# 0_STM32.net
KiCad netlist of a schematic drawn in Altium Designer
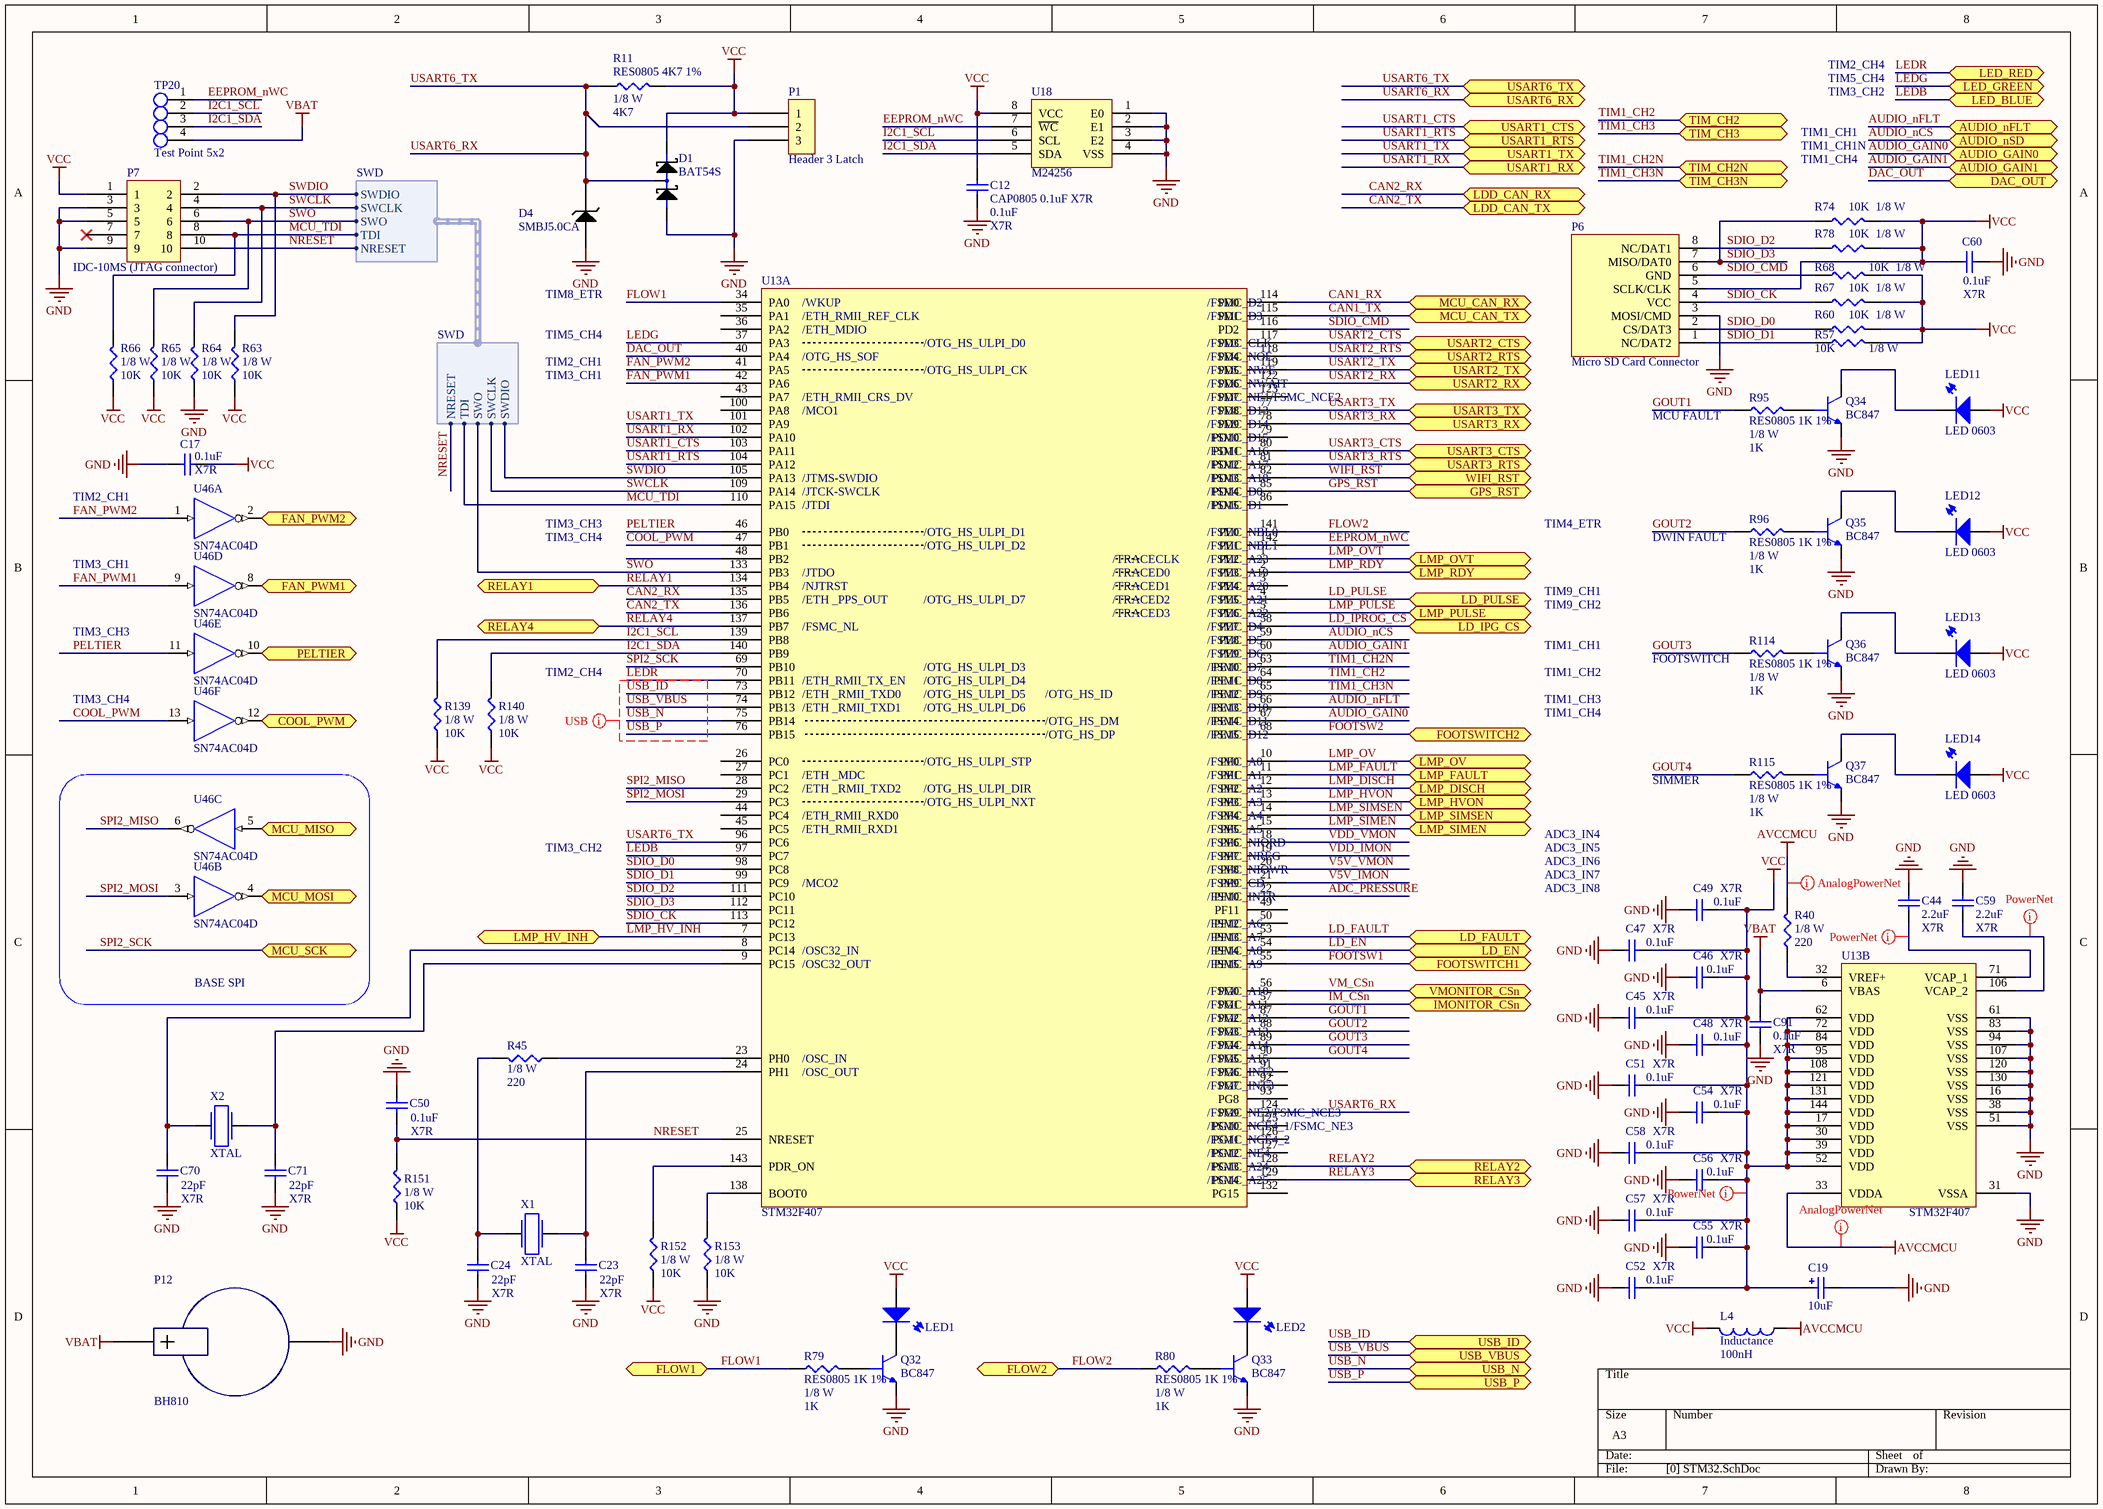
[diagram p0: [0] STM32.SchDoc]

(export (version "E")
  (design (tool "Eeschema 10.0.6"))
  (components
    (comp (ref "C12")
      (value "CAP0805 0.1uF X7R")
      (footprint "CAP0805")
      (description "Surface-mount ceramic multilayer capacitor")
      (fields
        (field (name "VOLTAGE") "50V")
        (field (name "TOLERANCE") "5%")
        (field (name "ALTIUM_VALUE") "0.1uF")
        (field (name "TYPE") "X7R")
      )
      (libsource (lib "Capacitors") (part "CAP0805 0.1uF X7R"))
    )
    (comp (ref "C17")
      (value "0.1uF")
      (footprint "CAP0805")
      (description "Surface-mount ceramic multilayer capacitor")
      (fields (field (name "VOLTAGE") "50V") (field (name "TOLERANCE") "10%") (field (name "TYPE") "X7R"))
      (libsource (lib "Capacitors") (part "CAP0805 0.01uF X7R"))
    )
    (comp (ref "C19")
      (value "10uF")
      (footprint "CAPC7343")
      (description "Polarized Capacitor (Radial)")
      (fields (field (name "Comment") "Cap Pol SMD"))
      (libsource (lib "Common Devices") (part "Cap Pol Chip"))
    )
    (comp (ref "C23")
      (value "22pF")
      (footprint "CAP0805")
      (description "Surface-mount ceramic multilayer capacitor")
      (fields (field (name "VOLTAGE") "50V") (field (name "TOLERANCE") "5%") (field (name "TYPE") "X7R"))
      (libsource (lib "Capacitors") (part "CAP0805 22pF X7R"))
    )
    (comp (ref "C24")
      (value "22pF")
      (footprint "CAP0805")
      (description "Surface-mount ceramic multilayer capacitor")
      (fields (field (name "VOLTAGE") "50V") (field (name "TOLERANCE") "5%") (field (name "TYPE") "X7R"))
      (libsource (lib "Capacitors") (part "CAP0805 22pF X7R"))
    )
    (comp (ref "C44")
      (value "2.2uF")
      (footprint "CAP0805")
      (description "Surface-mount ceramic multilayer capacitor")
      (fields (field (name "VOLTAGE") "50V") (field (name "TOLERANCE") "10%") (field (name "TYPE") "X7R"))
      (libsource (lib "Capacitors") (part "CAP0805 0.01uF X7R"))
    )
    (comp (ref "C45")
      (value "0.1uF")
      (footprint "CAP0805")
      (description "Surface-mount ceramic multilayer capacitor")
      (fields (field (name "VOLTAGE") "50V") (field (name "TOLERANCE") "10%") (field (name "TYPE") "X7R"))
      (libsource (lib "Capacitors") (part "CAP0805 0.01uF X7R"))
    )
    (comp (ref "C46")
      (value "0.1uF")
      (footprint "CAP0805")
      (description "Surface-mount ceramic multilayer capacitor")
      (fields (field (name "VOLTAGE") "50V") (field (name "TOLERANCE") "10%") (field (name "TYPE") "X7R"))
      (libsource (lib "Capacitors") (part "CAP0805 0.01uF X7R"))
    )
    (comp (ref "C47")
      (value "0.1uF")
      (footprint "CAP0805")
      (description "Surface-mount ceramic multilayer capacitor")
      (fields (field (name "VOLTAGE") "50V") (field (name "TOLERANCE") "10%") (field (name "TYPE") "X7R"))
      (libsource (lib "Capacitors") (part "CAP0805 0.01uF X7R"))
    )
    (comp (ref "C48")
      (value "0.1uF")
      (footprint "CAP0805")
      (description "Surface-mount ceramic multilayer capacitor")
      (fields (field (name "VOLTAGE") "50V") (field (name "TOLERANCE") "10%") (field (name "TYPE") "X7R"))
      (libsource (lib "Capacitors") (part "CAP0805 0.01uF X7R"))
    )
    (comp (ref "C49")
      (value "0.1uF")
      (footprint "CAP0805")
      (description "Surface-mount ceramic multilayer capacitor")
      (fields (field (name "VOLTAGE") "50V") (field (name "TOLERANCE") "10%") (field (name "TYPE") "X7R"))
      (libsource (lib "Capacitors") (part "CAP0805 0.01uF X7R"))
    )
    (comp (ref "C50")
      (value "0.1uF")
      (footprint "CAP0805")
      (description "Surface-mount ceramic multilayer capacitor")
      (fields (field (name "VOLTAGE") "50V") (field (name "TOLERANCE") "5%") (field (name "TYPE") "X7R"))
      (libsource (lib "Capacitors") (part "CAP0805 0.1uF X7R"))
    )
    (comp (ref "C51")
      (value "0.1uF")
      (footprint "CAP0805")
      (description "Surface-mount ceramic multilayer capacitor")
      (fields (field (name "VOLTAGE") "50V") (field (name "TOLERANCE") "10%") (field (name "TYPE") "X7R"))
      (libsource (lib "Capacitors") (part "CAP0805 0.01uF X7R"))
    )
    (comp (ref "C52")
      (value "0.1uF")
      (footprint "CAP0805")
      (description "Surface-mount ceramic multilayer capacitor")
      (fields (field (name "VOLTAGE") "50V") (field (name "TOLERANCE") "10%") (field (name "TYPE") "X7R"))
      (libsource (lib "Capacitors") (part "CAP0805 0.01uF X7R"))
    )
    (comp (ref "C54")
      (value "0.1uF")
      (footprint "CAP0805")
      (description "Surface-mount ceramic multilayer capacitor")
      (fields (field (name "VOLTAGE") "50V") (field (name "TOLERANCE") "10%") (field (name "TYPE") "X7R"))
      (libsource (lib "Capacitors") (part "CAP0805 0.01uF X7R"))
    )
    (comp (ref "C55")
      (value "0.1uF")
      (footprint "CAP0805")
      (description "Surface-mount ceramic multilayer capacitor")
      (fields (field (name "VOLTAGE") "50V") (field (name "TOLERANCE") "10%") (field (name "TYPE") "X7R"))
      (libsource (lib "Capacitors") (part "CAP0805 0.01uF X7R"))
    )
    (comp (ref "C56")
      (value "0.1uF")
      (footprint "CAP0805")
      (description "Surface-mount ceramic multilayer capacitor")
      (fields (field (name "VOLTAGE") "50V") (field (name "TOLERANCE") "10%") (field (name "TYPE") "X7R"))
      (libsource (lib "Capacitors") (part "CAP0805 0.01uF X7R"))
    )
    (comp (ref "C57")
      (value "0.1uF")
      (footprint "CAP0805")
      (description "Surface-mount ceramic multilayer capacitor")
      (fields (field (name "VOLTAGE") "50V") (field (name "TOLERANCE") "10%") (field (name "TYPE") "X7R"))
      (libsource (lib "Capacitors") (part "CAP0805 0.01uF X7R"))
    )
    (comp (ref "C58")
      (value "0.1uF")
      (footprint "CAP0805")
      (description "Surface-mount ceramic multilayer capacitor")
      (fields (field (name "VOLTAGE") "50V") (field (name "TOLERANCE") "10%") (field (name "TYPE") "X7R"))
      (libsource (lib "Capacitors") (part "CAP0805 0.01uF X7R"))
    )
    (comp (ref "C59")
      (value "2.2uF")
      (footprint "CAP0805")
      (description "Surface-mount ceramic multilayer capacitor")
      (fields (field (name "VOLTAGE") "50V") (field (name "TOLERANCE") "10%") (field (name "TYPE") "X7R"))
      (libsource (lib "Capacitors") (part "CAP0805 0.01uF X7R"))
    )
    (comp (ref "C60")
      (value "0.1uF")
      (footprint "CAP0805")
      (description "Surface-mount ceramic multilayer capacitor")
      (fields (field (name "VOLTAGE") "50V") (field (name "TOLERANCE") "5%") (field (name "TYPE") "X7R"))
      (libsource (lib "Capacitors") (part "CAP0805 0.1uF X7R"))
    )
    (comp (ref "C70")
      (value "22pF")
      (footprint "CAP0805")
      (description "Surface-mount ceramic multilayer capacitor")
      (fields (field (name "VOLTAGE") "50V") (field (name "TOLERANCE") "5%") (field (name "TYPE") "X7R"))
      (libsource (lib "Capacitors") (part "CAP0805 22pF X7R"))
    )
    (comp (ref "C71")
      (value "22pF")
      (footprint "CAP0805")
      (description "Surface-mount ceramic multilayer capacitor")
      (fields (field (name "VOLTAGE") "50V") (field (name "TOLERANCE") "5%") (field (name "TYPE") "X7R"))
      (libsource (lib "Capacitors") (part "CAP0805 22pF X7R"))
    )
    (comp (ref "C91")
      (value "0.1uF")
      (footprint "CAP0805")
      (description "Surface-mount ceramic multilayer capacitor")
      (fields (field (name "VOLTAGE") "50V") (field (name "TOLERANCE") "10%") (field (name "TYPE") "X7R"))
      (libsource (lib "Capacitors") (part "CAP0805 0.01uF X7R"))
    )
    (comp (ref "D1")
      (value "BAT54S")
      (footprint "SOT23")
      (description "Small signal schottky dual diode")
      (fields (field (name "MANUFACTURER PART NUMBER") "BAT54S-V-GS08") (field (name "VOLTAGE") "30"))
      (libsource (lib "Protection") (part "BAT54S"))
    )
    (comp (ref "D4")
      (value "SMBJ5.0CA")
      (footprint "DO-214AS")
      (description "Transient Voltage Suppressor 600W uni-directional")
      (fields (field (name "VOLTAGE") "5.0V"))
      (libsource (lib "Protection") (part "SMBJ5.0CA"))
    )
    (comp (ref "L4")
      (value "Inductance")
      (footprint "CM45")
      (fields (field (name "ALTIUM_VALUE") "100nH"))
      (libsource (lib "Common Devices") (part "ChipInductance"))
    )
    (comp (ref "LED1") (value "LED 0603") (footprint "LED 0603") (libsource (lib "LEDs") (part "LED0603")))
    (comp (ref "LED2") (value "LED 0603") (footprint "LED 0603") (libsource (lib "LEDs") (part "LED0603")))
    (comp (ref "LED11") (value "LED 0603") (footprint "PLCC-2") (libsource (lib "LEDs") (part "LED0603")))
    (comp (ref "LED12") (value "LED 0603") (footprint "PLCC-2") (libsource (lib "LEDs") (part "LED0603")))
    (comp (ref "LED13") (value "LED 0603") (footprint "PLCC-2") (libsource (lib "LEDs") (part "LED0603")))
    (comp (ref "LED14") (value "LED 0603") (footprint "PLCC-2") (libsource (lib "LEDs") (part "LED0603")))
    (comp (ref "P1")
      (value "Header 3 Latch")
      (footprint "Header 3 latch")
      (description "Header 3 with latch")
      (libsource (lib "IndustrialConnectors") (part "Header 3 latch"))
    )
    (comp (ref "P6")
      (value "Micro SD Card Connector")
      (footprint "WR-CRD SD Micro")
      (libsource (lib "Connectors") (part "MicroSDHeader8"))
    )
    (comp (ref "P7")
      (value "IDC-10MS (JTAG connector)")
      (footprint "IDC-10MS(MR)")
      (libsource (lib "Connectors") (part "IDC-10MS (JTAG connector)"))
    )
    (comp (ref "P12") (value "BH810") (footprint "BH810") (libsource (lib "BatteryHolder") (part "BH810")))
    (comp (ref "Q32")
      (value "BC847")
      (footprint "SOT23")
      (description "NPN transistor")
      (fields (field (name "MANUFACTURER") "ONS") (field (name "MANUFACTURER PART NUMBER") "BC847BLT1G"))
      (libsource (lib "BJT") (part "BC847"))
    )
    (comp (ref "Q33")
      (value "BC847")
      (footprint "SOT23")
      (description "NPN transistor")
      (fields (field (name "MANUFACTURER") "ONS") (field (name "MANUFACTURER PART NUMBER") "BC847BLT1G"))
      (libsource (lib "BJT") (part "BC847"))
    )
    (comp (ref "Q34")
      (value "BC847")
      (footprint "SOT23")
      (description "NPN transistor")
      (fields (field (name "MANUFACTURER") "ONS") (field (name "MANUFACTURER PART NUMBER") "BC847BLT1G"))
      (libsource (lib "BJT") (part "BC847"))
    )
    (comp (ref "Q35")
      (value "BC847")
      (footprint "SOT23")
      (description "NPN transistor")
      (fields (field (name "MANUFACTURER") "ONS") (field (name "MANUFACTURER PART NUMBER") "BC847BLT1G"))
      (libsource (lib "BJT") (part "BC847"))
    )
    (comp (ref "Q36")
      (value "BC847")
      (footprint "SOT23")
      (description "NPN transistor")
      (fields (field (name "MANUFACTURER") "ONS") (field (name "MANUFACTURER PART NUMBER") "BC847BLT1G"))
      (libsource (lib "BJT") (part "BC847"))
    )
    (comp (ref "Q37")
      (value "BC847")
      (footprint "SOT23")
      (description "NPN transistor")
      (fields (field (name "MANUFACTURER") "ONS") (field (name "MANUFACTURER PART NUMBER") "BC847BLT1G"))
      (libsource (lib "BJT") (part "BC847"))
    )
    (comp (ref "R11")
      (value "RES0805 4K7 1%")
      (footprint "RES0805")
      (description "Think Film Chip resistor")
      (fields
        (field (name "TOLERANCE") "1%")
        (field (name "MANUFACTURER PART NUMBER") "RC0805FR-074K7L")
        (field (name "RATING") "1/8 W")
        (field (name "ALTIUM_VALUE") "4K7")
      )
      (libsource (lib "Resistors") (part "RES0805 4K7 1%"))
    )
    (comp (ref "R40")
      (value "220")
      (footprint "RES0805")
      (description "Think Film Chip resistor")
      (fields
        (field (name "TOLERANCE") "1%")
        (field (name "MANUFACTURER PART NUMBER") "RC0805JR-07220R")
        (field (name "RATING") "1/8 W")
      )
      (libsource (lib "Resistors") (part "RES0805 220R 1%"))
    )
    (comp (ref "R45")
      (value "220")
      (footprint "RES0805")
      (description "Think Film Chip resistor")
      (fields
        (field (name "TOLERANCE") "1%")
        (field (name "MANUFACTURER PART NUMBER") "RC0805JR-07220R")
        (field (name "RATING") "1/8 W")
      )
      (libsource (lib "Resistors") (part "RES0805 220R 1%"))
    )
    (comp (ref "R57")
      (value "10K")
      (footprint "RES0805")
      (description "Think Film Chip resistor")
      (fields
        (field (name "TOLERANCE") "1%")
        (field (name "MANUFACTURER PART NUMBER") "RC0805FR-0710KL")
        (field (name "RATING") "1/8 W")
      )
      (libsource (lib "Resistors") (part "RES0805 10K 1%"))
    )
    (comp (ref "R60")
      (value "10K")
      (footprint "RES0805")
      (description "Think Film Chip resistor")
      (fields
        (field (name "TOLERANCE") "1%")
        (field (name "MANUFACTURER PART NUMBER") "RC0805FR-0710KL")
        (field (name "RATING") "1/8 W")
      )
      (libsource (lib "Resistors") (part "RES0805 10K 1%"))
    )
    (comp (ref "R63")
      (value "10K")
      (footprint "RES0805")
      (description "Think Film Chip resistor")
      (fields
        (field (name "TOLERANCE") "1%")
        (field (name "MANUFACTURER PART NUMBER") "RC0805FR-0710KL")
        (field (name "RATING") "1/8 W")
      )
      (libsource (lib "Resistors") (part "RES0805 10K 1%"))
    )
    (comp (ref "R64")
      (value "10K")
      (footprint "RES0805")
      (description "Think Film Chip resistor")
      (fields
        (field (name "TOLERANCE") "1%")
        (field (name "MANUFACTURER PART NUMBER") "RC0805FR-0710KL")
        (field (name "RATING") "1/8 W")
      )
      (libsource (lib "Resistors") (part "RES0805 10K 1%"))
    )
    (comp (ref "R65")
      (value "10K")
      (footprint "RES0805")
      (description "Think Film Chip resistor")
      (fields
        (field (name "TOLERANCE") "1%")
        (field (name "MANUFACTURER PART NUMBER") "RC0805FR-0710KL")
        (field (name "RATING") "1/8 W")
      )
      (libsource (lib "Resistors") (part "RES0805 10K 1%"))
    )
    (comp (ref "R66")
      (value "10K")
      (footprint "RES0805")
      (description "Think Film Chip resistor")
      (fields
        (field (name "TOLERANCE") "1%")
        (field (name "MANUFACTURER PART NUMBER") "RC0805FR-0710KL")
        (field (name "RATING") "1/8 W")
      )
      (libsource (lib "Resistors") (part "RES0805 10K 1%"))
    )
    (comp (ref "R67")
      (value "10K")
      (footprint "RES0805")
      (description "Think Film Chip resistor")
      (fields
        (field (name "TOLERANCE") "1%")
        (field (name "MANUFACTURER PART NUMBER") "RC0805FR-0710KL")
        (field (name "RATING") "1/8 W")
      )
      (libsource (lib "Resistors") (part "RES0805 10K 1%"))
    )
    (comp (ref "R68")
      (value "10K")
      (footprint "RES0805")
      (description "Think Film Chip resistor")
      (fields
        (field (name "TOLERANCE") "1%")
        (field (name "MANUFACTURER PART NUMBER") "RC0805FR-0710KL")
        (field (name "RATING") "1/8 W")
      )
      (libsource (lib "Resistors") (part "RES0805 10K 1%"))
    )
    (comp (ref "R74")
      (value "10K")
      (footprint "RES0805")
      (description "Think Film Chip resistor")
      (fields
        (field (name "TOLERANCE") "1%")
        (field (name "MANUFACTURER PART NUMBER") "RC0805FR-0710KL")
        (field (name "RATING") "1/8 W")
      )
      (libsource (lib "Resistors") (part "RES0805 10K 1%"))
    )
    (comp (ref "R78")
      (value "10K")
      (footprint "RES0805")
      (description "Think Film Chip resistor")
      (fields
        (field (name "TOLERANCE") "1%")
        (field (name "MANUFACTURER PART NUMBER") "RC0805FR-0710KL")
        (field (name "RATING") "1/8 W")
      )
      (libsource (lib "Resistors") (part "RES0805 10K 1%"))
    )
    (comp (ref "R79")
      (value "RES0805 1K 1%")
      (footprint "RES0805")
      (description "Think Film Chip resistor")
      (fields
        (field (name "TOLERANCE") "1%")
        (field (name "MANUFACTURER PART NUMBER") "RC0805FR-071KL")
        (field (name "RATING") "1/8 W")
        (field (name "ALTIUM_VALUE") "1K")
      )
      (libsource (lib "Resistors") (part "RES0805 1K 1%"))
    )
    (comp (ref "R80")
      (value "RES0805 1K 1%")
      (footprint "RES0805")
      (description "Think Film Chip resistor")
      (fields
        (field (name "TOLERANCE") "1%")
        (field (name "MANUFACTURER PART NUMBER") "RC0805FR-071KL")
        (field (name "RATING") "1/8 W")
        (field (name "ALTIUM_VALUE") "1K")
      )
      (libsource (lib "Resistors") (part "RES0805 1K 1%"))
    )
    (comp (ref "R95")
      (value "RES0805 1K 1%")
      (footprint "RES0805")
      (description "Think Film Chip resistor")
      (fields
        (field (name "TOLERANCE") "1%")
        (field (name "MANUFACTURER PART NUMBER") "RC0805FR-071KL")
        (field (name "RATING") "1/8 W")
        (field (name "ALTIUM_VALUE") "1K")
      )
      (libsource (lib "Resistors") (part "RES0805 1K 1%"))
    )
    (comp (ref "R96")
      (value "RES0805 1K 1%")
      (footprint "RES0805")
      (description "Think Film Chip resistor")
      (fields
        (field (name "TOLERANCE") "1%")
        (field (name "MANUFACTURER PART NUMBER") "RC0805FR-071KL")
        (field (name "RATING") "1/8 W")
        (field (name "ALTIUM_VALUE") "1K")
      )
      (libsource (lib "Resistors") (part "RES0805 1K 1%"))
    )
    (comp (ref "R114")
      (value "RES0805 1K 1%")
      (footprint "RES0805")
      (description "Think Film Chip resistor")
      (fields
        (field (name "TOLERANCE") "1%")
        (field (name "MANUFACTURER PART NUMBER") "RC0805FR-071KL")
        (field (name "RATING") "1/8 W")
        (field (name "ALTIUM_VALUE") "1K")
      )
      (libsource (lib "Resistors") (part "RES0805 1K 1%"))
    )
    (comp (ref "R115")
      (value "RES0805 1K 1%")
      (footprint "RES0805")
      (description "Think Film Chip resistor")
      (fields
        (field (name "TOLERANCE") "1%")
        (field (name "MANUFACTURER PART NUMBER") "RC0805FR-071KL")
        (field (name "RATING") "1/8 W")
        (field (name "ALTIUM_VALUE") "1K")
      )
      (libsource (lib "Resistors") (part "RES0805 1K 1%"))
    )
    (comp (ref "R139")
      (value "10K")
      (footprint "RES0805")
      (description "Think Film Chip resistor")
      (fields
        (field (name "TOLERANCE") "1%")
        (field (name "MANUFACTURER PART NUMBER") "RC0805FR-0710KL")
        (field (name "RATING") "1/8 W")
      )
      (libsource (lib "Resistors") (part "RES0805 10K 1%"))
    )
    (comp (ref "R140")
      (value "10K")
      (footprint "RES0805")
      (description "Think Film Chip resistor")
      (fields
        (field (name "TOLERANCE") "1%")
        (field (name "MANUFACTURER PART NUMBER") "RC0805FR-0710KL")
        (field (name "RATING") "1/8 W")
      )
      (libsource (lib "Resistors") (part "RES0805 10K 1%"))
    )
    (comp (ref "R151")
      (value "10K")
      (footprint "RES0805")
      (description "Think Film Chip resistor")
      (fields
        (field (name "TOLERANCE") "1%")
        (field (name "MANUFACTURER PART NUMBER") "RC0805FR-0710KL")
        (field (name "RATING") "1/8 W")
      )
      (libsource (lib "Resistors") (part "RES0805 10K 1%"))
    )
    (comp (ref "R152")
      (value "10K")
      (footprint "RES0805")
      (description "Think Film Chip resistor")
      (fields
        (field (name "TOLERANCE") "1%")
        (field (name "MANUFACTURER PART NUMBER") "RC0805FR-0710KL")
        (field (name "RATING") "1/8 W")
      )
      (libsource (lib "Resistors") (part "RES0805 10K 1%"))
    )
    (comp (ref "R153")
      (value "10K")
      (footprint "RES0805")
      (description "Think Film Chip resistor")
      (fields
        (field (name "TOLERANCE") "1%")
        (field (name "MANUFACTURER PART NUMBER") "RC0805FR-0710KL")
        (field (name "RATING") "1/8 W")
      )
      (libsource (lib "Resistors") (part "RES0805 10K 1%"))
    )
    (comp (ref "TP20")
      (value "Test Point 5x2")
      (footprint "PG-1.5-13.5-4P-2.54PH")
      (libsource (lib "Connectors") (part "PG-1.5-13.5-4P-2.54PH"))
    )
    (comp (ref "U13")
      (value "STM32F407")
      (footprint "LQFP144")
      (description "ST Microcontroller ARM 32-bit Cortex M4")
      (libsource (lib "ST ARM32") (part "STM32F407ZGT6"))
    )
    (comp (ref "U18")
      (value "M24256")
      (footprint "SOIC8")
      (description "256 Kbit I2C EEPROM")
      (libsource (lib "ST EEPROM") (part "M24256"))
    )
    (comp (ref "U46")
      (value "SN74AC04D")
      (footprint "D014_N")
      (description "Hex Inverter")
      (fields (field (name "PUBLISHER") "Altium Limited"))
      (libsource (lib "TI Logic Gate 1") (part "SN74AC04D"))
    )
    (comp (ref "X1")
      (value "XTAL")
      (footprint "BCY-W2/E4.7")
      (description "Quartz crystall oscillator")
      (libsource (lib "Common Devices") (part "Crystall oscillator"))
    )
    (comp (ref "X2")
      (value "XTAL")
      (footprint "KX-327NHT")
      (description "Quartz crystal oscillator 32.768kHz")
      (fields
        (field (name "MANUFACTURER PART NUMBER") "KX-327NHT 32.768 kHz")
        (field (name "TOLERANCE") "20ppm")
      )
      (libsource (lib "Common Devices") (part "KX-327NHT"))
    )
  )
  (nets
    (net (code "2") (name "/ADC_PRESSURE") (class "Default")
      (node (ref "U13") (pin "22") (pinfunction "PF10_22") (pintype "passive"))
    )
    (net (code "3") (name "/AUDIO_GAIN0") (class "Default")
      (node (ref "U13") (pin "67") (pinfunction "PE14_67") (pintype "passive"))
    )
    (net (code "4") (name "/AUDIO_GAIN1") (class "Default")
      (node (ref "U13") (pin "60") (pinfunction "PE9_60") (pintype "passive"))
    )
    (net (code "5") (name "/AUDIO_nCS") (class "Default")
      (node (ref "U13") (pin "59") (pinfunction "PE8_59") (pintype "passive"))
    )
    (net (code "6") (name "/AUDIO_nFLT") (class "Default")
      (node (ref "U13") (pin "66") (pinfunction "PE13_66") (pintype "passive"))
    )
    (net (code "7") (name "/CAN1_RX") (class "Default")
      (node (ref "U13") (pin "114") (pinfunction "PD0_114") (pintype "passive"))
    )
    (net (code "8") (name "/CAN1_TX") (class "Default")
      (node (ref "U13") (pin "115") (pinfunction "PD1_115") (pintype "passive"))
    )
    (net (code "9") (name "/CAN2_RX") (class "Default")
      (node (ref "U13") (pin "135") (pinfunction "PB5_135") (pintype "passive"))
    )
    (net (code "10") (name "/CAN2_TX") (class "Default")
      (node (ref "U13") (pin "136") (pinfunction "PB6_136") (pintype "passive"))
    )
    (net (code "11") (name "/COOL_PWM") (class "Default")
      (node (ref "U13") (pin "47") (pinfunction "PB1_47") (pintype "passive"))
      (node (ref "U46") (pin "13") (pinfunction "A_13") (pintype "input"))
    )
    (net (code "12") (name "/DAC_OUT") (class "Default")
      (node (ref "U13") (pin "40") (pinfunction "PA4_40") (pintype "passive"))
    )
    (net (code "13") (name "/EEPROM_nWC") (class "Default")
      (node (ref "TP20") (pin "1") (pinfunction "1_1") (pintype "passive"))
      (node (ref "U13") (pin "142") (pinfunction "PE1_142") (pintype "passive"))
      (node (ref "U18") (pin "7") (pinfunction "~{WC}_7") (pintype "passive"))
    )
    (net (code "14") (name "/FAN_PWM1") (class "Default")
      (node (ref "U13") (pin "42") (pinfunction "PA6_42") (pintype "passive"))
      (node (ref "U46") (pin "9") (pinfunction "A_9") (pintype "input"))
    )
    (net (code "15") (name "/FAN_PWM2") (class "Default")
      (node (ref "U13") (pin "41") (pinfunction "PA5_41") (pintype "passive"))
      (node (ref "U46") (pin "1") (pinfunction "A_1") (pintype "input"))
    )
    (net (code "16") (name "/FLOW1") (class "Default")
      (node (ref "R79") (pin "1") (pintype "passive"))
      (node (ref "U13") (pin "34") (pinfunction "PA0_34") (pintype "passive"))
    )
    (net (code "17") (name "/FLOW2") (class "Default")
      (node (ref "R80") (pin "1") (pintype "passive"))
      (node (ref "U13") (pin "141") (pinfunction "PE0_141") (pintype "passive"))
    )
    (net (code "18") (name "/FOOTSW1") (class "Default")
      (node (ref "U13") (pin "55") (pinfunction "PF15_55") (pintype "passive"))
    )
    (net (code "19") (name "/FOOTSW2") (class "Default")
      (node (ref "U13") (pin "68") (pinfunction "PE15_68") (pintype "passive"))
    )
    (net (code "20") (name "/GOUT1") (class "Default")
      (node (ref "R95") (pin "1") (pintype "passive"))
      (node (ref "U13") (pin "87") (pinfunction "PG2_87") (pintype "passive"))
    )
    (net (code "21") (name "/GOUT2") (class "Default")
      (node (ref "R96") (pin "1") (pintype "passive"))
      (node (ref "U13") (pin "88") (pinfunction "PG3_88") (pintype "passive"))
    )
    (net (code "22") (name "/GOUT3") (class "Default")
      (node (ref "R114") (pin "1") (pintype "passive"))
      (node (ref "U13") (pin "89") (pinfunction "PG4_89") (pintype "passive"))
    )
    (net (code "23") (name "/GOUT4") (class "Default")
      (node (ref "R115") (pin "1") (pintype "passive"))
      (node (ref "U13") (pin "90") (pinfunction "PG5_90") (pintype "passive"))
    )
    (net (code "24") (name "/GPS_RST") (class "Default")
      (node (ref "U13") (pin "85") (pinfunction "PD14_85") (pintype "passive"))
    )
    (net (code "25") (name "/I2C1_SCL") (class "Default")
      (node (ref "R139") (pin "2") (pintype "passive"))
      (node (ref "TP20") (pin "2") (pinfunction "2_2") (pintype "passive"))
      (node (ref "U13") (pin "139") (pinfunction "PB8_139") (pintype "passive"))
      (node (ref "U18") (pin "6") (pinfunction "SCL_6") (pintype "passive"))
    )
    (net (code "26") (name "/I2C1_SDA") (class "Default")
      (node (ref "R140") (pin "2") (pintype "passive"))
      (node (ref "TP20") (pin "3") (pinfunction "3_3") (pintype "passive"))
      (node (ref "U13") (pin "140") (pinfunction "PB9_140") (pintype "passive"))
      (node (ref "U18") (pin "5") (pinfunction "SDA_5") (pintype "passive"))
    )
    (net (code "27") (name "/IM_CSn") (class "Default")
      (node (ref "U13") (pin "57") (pinfunction "PG1_57") (pintype "passive"))
    )
    (net (code "28") (name "/LD_EN") (class "Default")
      (node (ref "U13") (pin "54") (pinfunction "PF14_54") (pintype "passive"))
    )
    (net (code "29") (name "/LD_FAULT") (class "Default")
      (node (ref "U13") (pin "53") (pinfunction "PF13_53") (pintype "passive"))
    )
    (net (code "30") (name "/LD_IPROG_CS") (class "Default")
      (node (ref "U13") (pin "58") (pinfunction "PE7_58") (pintype "passive"))
    )
    (net (code "31") (name "/LD_PULSE") (class "Default")
      (node (ref "U13") (pin "4") (pinfunction "PE5_4") (pintype "passive"))
    )
    (net (code "32") (name "/LEDB") (class "Default")
      (node (ref "U13") (pin "97") (pinfunction "PC7_97") (pintype "passive"))
    )
    (net (code "33") (name "/LEDG") (class "Default")
      (node (ref "U13") (pin "37") (pinfunction "PA3_37") (pintype "passive"))
    )
    (net (code "34") (name "/LEDR") (class "Default")
      (node (ref "U13") (pin "70") (pinfunction "PB11_70") (pintype "passive"))
    )
    (net (code "35") (name "/LMP_DISCH") (class "Default")
      (node (ref "U13") (pin "12") (pinfunction "PF2_12") (pintype "passive"))
    )
    (net (code "36") (name "/LMP_FAULT") (class "Default")
      (node (ref "U13") (pin "11") (pinfunction "PF1_11") (pintype "passive"))
    )
    (net (code "37") (name "/LMP_HVON") (class "Default")
      (node (ref "U13") (pin "13") (pinfunction "PF3_13") (pintype "passive"))
    )
    (net (code "38") (name "/LMP_HV_INH") (class "Default")
      (node (ref "U13") (pin "7") (pinfunction "PC13_7") (pintype "passive"))
    )
    (net (code "39") (name "/LMP_OV") (class "Default")
      (node (ref "U13") (pin "10") (pinfunction "PF0_10") (pintype "passive"))
    )
    (net (code "40") (name "/LMP_OVT") (class "Default")
      (node (ref "U13") (pin "1") (pinfunction "PE2_1") (pintype "passive"))
    )
    (net (code "41") (name "/LMP_PULSE") (class "Default")
      (node (ref "U13") (pin "5") (pinfunction "PE6_5") (pintype "passive"))
    )
    (net (code "42") (name "/LMP_RDY") (class "Default")
      (node (ref "U13") (pin "2") (pinfunction "PE3_2") (pintype "passive"))
    )
    (net (code "43") (name "/LMP_SIMEN") (class "Default")
      (node (ref "U13") (pin "15") (pinfunction "PF5_15") (pintype "passive"))
    )
    (net (code "44") (name "/LMP_SIMSEN") (class "Default")
      (node (ref "U13") (pin "14") (pinfunction "PF4_14") (pintype "passive"))
    )
    (net (code "45") (name "/MCU_MISO") (class "Default")
      (node (ref "U46") (pin "5") (pinfunction "A_5") (pintype "input"))
    )
    (net (code "46") (name "/MCU_MOSI") (class "Default")
      (node (ref "U46") (pin "4") (pinfunction "Y_4") (pintype "output"))
    )
    (net (code "47") (name "/MCU_TDI") (class "Default")
      (node (ref "P7") (pin "8") (pinfunction "8_8") (pintype "passive"))
      (node (ref "R66") (pin "2") (pintype "passive"))
      (node (ref "U13") (pin "110") (pinfunction "PA15_110") (pintype "passive"))
    )
    (net (code "48") (name "/NRESET") (class "Default")
      (node (ref "C50") (pin "1") (pinfunction "1_1") (pintype "passive"))
      (node (ref "P7") (pin "10") (pinfunction "10_10") (pintype "passive"))
      (node (ref "R151") (pin "2") (pintype "passive"))
      (node (ref "U13") (pin "25") (pinfunction "NRESET_25") (pintype "passive"))
    )
    (net (code "49") (name "/PELTIER") (class "Default")
      (node (ref "U13") (pin "46") (pinfunction "PB0_46") (pintype "passive"))
      (node (ref "U46") (pin "11") (pinfunction "A_11") (pintype "input"))
    )
    (net (code "50") (name "/RELAY1") (class "Default")
      (node (ref "U13") (pin "134") (pinfunction "PB4_134") (pintype "passive"))
    )
    (net (code "51") (name "/RELAY2") (class "Default")
      (node (ref "U13") (pin "128") (pinfunction "PG13_128") (pintype "passive"))
    )
    (net (code "52") (name "/RELAY3") (class "Default")
      (node (ref "U13") (pin "129") (pinfunction "PG14_129") (pintype "passive"))
    )
    (net (code "53") (name "/RELAY4") (class "Default")
      (node (ref "U13") (pin "137") (pinfunction "PB7_137") (pintype "passive"))
    )
    (net (code "54") (name "/SDIO_CK") (class "Default")
      (node (ref "P6") (pin "4") (pinfunction "VCC_4") (pintype "passive"))
      (node (ref "R67") (pin "1") (pintype "passive"))
      (node (ref "U13") (pin "113") (pinfunction "PC12_113") (pintype "passive"))
    )
    (net (code "55") (name "/SDIO_CMD") (class "Default")
      (node (ref "P6") (pin "6") (pinfunction "GND_6") (pintype "passive"))
      (node (ref "R68") (pin "1") (pintype "passive"))
      (node (ref "U13") (pin "116") (pinfunction "PD2_116") (pintype "passive"))
    )
    (net (code "56") (name "/SDIO_D0") (class "Default")
      (node (ref "P6") (pin "2") (pinfunction "CS/DAT3_2") (pintype "passive"))
      (node (ref "R60") (pin "1") (pintype "passive"))
      (node (ref "U13") (pin "98") (pinfunction "PC8_98") (pintype "passive"))
    )
    (net (code "57") (name "/SDIO_D1") (class "Default")
      (node (ref "P6") (pin "1") (pinfunction "NC/DAT2_1") (pintype "passive"))
      (node (ref "R57") (pin "1") (pintype "passive"))
      (node (ref "U13") (pin "99") (pinfunction "PC9_99") (pintype "passive"))
    )
    (net (code "58") (name "/SDIO_D2") (class "Default")
      (node (ref "P6") (pin "8") (pinfunction "NC/DAT1_8") (pintype "passive"))
      (node (ref "R78") (pin "1") (pintype "passive"))
      (node (ref "U13") (pin "111") (pinfunction "PC10_111") (pintype "passive"))
    )
    (net (code "59") (name "/SDIO_D3") (class "Default")
      (node (ref "P6") (pin "7") (pinfunction "MISO/DAT0_7") (pintype "passive"))
      (node (ref "R74") (pin "1") (pintype "passive"))
      (node (ref "U13") (pin "112") (pinfunction "PC11_112") (pintype "passive"))
    )
    (net (code "60") (name "/SPI2_MISO") (class "Default")
      (node (ref "U13") (pin "28") (pinfunction "PC2_28") (pintype "passive"))
      (node (ref "U46") (pin "6") (pinfunction "Y_6") (pintype "output"))
    )
    (net (code "61") (name "/SPI2_MOSI") (class "Default")
      (node (ref "U13") (pin "29") (pinfunction "PC3_29") (pintype "passive"))
      (node (ref "U46") (pin "3") (pinfunction "A_3") (pintype "input"))
    )
    (net (code "62") (name "/SPI2_SCK") (class "Default")
      (node (ref "U13") (pin "69") (pinfunction "PB10_69") (pintype "passive"))
    )
    (net (code "63") (name "/SWCLK") (class "Default")
      (node (ref "P7") (pin "4") (pinfunction "4_4") (pintype "passive"))
      (node (ref "R64") (pin "2") (pintype "passive"))
      (node (ref "U13") (pin "109") (pinfunction "PA14_109") (pintype "passive"))
    )
    (net (code "64") (name "/SWDIO") (class "Default")
      (node (ref "P7") (pin "2") (pinfunction "2_2") (pintype "passive"))
      (node (ref "R63") (pin "2") (pintype "passive"))
      (node (ref "U13") (pin "105") (pinfunction "PA13_105") (pintype "passive"))
    )
    (net (code "65") (name "/SWO") (class "Default")
      (node (ref "P7") (pin "6") (pinfunction "6_6") (pintype "passive"))
      (node (ref "R65") (pin "2") (pintype "passive"))
      (node (ref "U13") (pin "133") (pinfunction "PB3_133") (pintype "passive"))
    )
    (net (code "66") (name "/TIM1_CH2") (class "Default")
      (node (ref "U13") (pin "64") (pinfunction "PE11_64") (pintype "passive"))
    )
    (net (code "67") (name "/TIM1_CH2N") (class "Default")
      (node (ref "U13") (pin "63") (pinfunction "PE10_63") (pintype "passive"))
    )
    (net (code "69") (name "/TIM1_CH3N") (class "Default")
      (node (ref "U13") (pin "65") (pinfunction "PE12_65") (pintype "passive"))
    )
    (net (code "70") (name "/USART1_CTS") (class "Default")
      (node (ref "U13") (pin "103") (pinfunction "PA11_103") (pintype "passive"))
    )
    (net (code "71") (name "/USART1_RTS") (class "Default")
      (node (ref "U13") (pin "104") (pinfunction "PA12_104") (pintype "passive"))
    )
    (net (code "72") (name "/USART1_RX") (class "Default")
      (node (ref "U13") (pin "102") (pinfunction "PA10_102") (pintype "passive"))
    )
    (net (code "73") (name "/USART1_TX") (class "Default")
      (node (ref "U13") (pin "101") (pinfunction "PA9_101") (pintype "passive"))
    )
    (net (code "74") (name "/USART2_CTS") (class "Default")
      (node (ref "U13") (pin "117") (pinfunction "PD3_117") (pintype "passive"))
    )
    (net (code "75") (name "/USART2_RTS") (class "Default")
      (node (ref "U13") (pin "118") (pinfunction "PD4_118") (pintype "passive"))
    )
    (net (code "76") (name "/USART2_RX") (class "Default")
      (node (ref "U13") (pin "122") (pinfunction "PD6_122") (pintype "passive"))
    )
    (net (code "77") (name "/USART2_TX") (class "Default")
      (node (ref "U13") (pin "119") (pinfunction "PD5_119") (pintype "passive"))
    )
    (net (code "78") (name "/USART3_CTS") (class "Default")
      (node (ref "U13") (pin "80") (pinfunction "PD11_80") (pintype "passive"))
    )
    (net (code "79") (name "/USART3_RTS") (class "Default")
      (node (ref "U13") (pin "81") (pinfunction "PD12_81") (pintype "passive"))
    )
    (net (code "80") (name "/USART3_RX") (class "Default")
      (node (ref "U13") (pin "78") (pinfunction "PD9_78") (pintype "passive"))
    )
    (net (code "81") (name "/USART3_TX") (class "Default")
      (node (ref "U13") (pin "77") (pinfunction "PD8_77") (pintype "passive"))
    )
    (net (code "82") (name "/USART6_RX") (class "Default")
      (node (ref "D1") (pin "3") (pinfunction "3_3") (pintype "passive"))
      (node (ref "D4") (pin "1") (pinfunction "1_1") (pintype "passive"))
      (node (ref "P1") (pin "2") (pinfunction "2_2") (pintype "passive"))
      (node (ref "R11") (pin "1") (pintype "passive"))
      (node (ref "U13") (pin "124") (pinfunction "PG9_124") (pintype "passive"))
      (node (ref "U13") (pin "96") (pinfunction "PC6_96") (pintype "passive"))
    )
    (net (code "83") (name "/USB_ID") (class "Default")
      (node (ref "U13") (pin "73") (pinfunction "PB12_73") (pintype "passive"))
    )
    (net (code "84") (name "/USB_N") (class "Default")
      (node (ref "U13") (pin "75") (pinfunction "PB14_75") (pintype "passive"))
    )
    (net (code "85") (name "/USB_P") (class "Default")
      (node (ref "U13") (pin "76") (pinfunction "PB15_76") (pintype "passive"))
    )
    (net (code "86") (name "/USB_VBUS") (class "Default")
      (node (ref "U13") (pin "74") (pinfunction "PB13_74") (pintype "passive"))
    )
    (net (code "87") (name "/V5V_IMON") (class "Default")
      (node (ref "U13") (pin "21") (pinfunction "PF9_21") (pintype "passive"))
    )
    (net (code "88") (name "/V5V_VMON") (class "Default")
      (node (ref "U13") (pin "20") (pinfunction "PF8_20") (pintype "passive"))
    )
    (net (code "89") (name "/VDD_IMON") (class "Default")
      (node (ref "U13") (pin "19") (pinfunction "PF7_19") (pintype "passive"))
    )
    (net (code "90") (name "/VDD_VMON") (class "Default")
      (node (ref "U13") (pin "18") (pinfunction "PF6_18") (pintype "passive"))
    )
    (net (code "91") (name "/VM_CSn") (class "Default")
      (node (ref "U13") (pin "56") (pinfunction "PG0_56") (pintype "passive"))
    )
    (net (code "92") (name "/WIFI_RST") (class "Default")
      (node (ref "U13") (pin "82") (pinfunction "PD13_82") (pintype "passive"))
    )
    (net (code "94") (name "AVCCMCU") (class "Default")
      (node (ref "L4") (pin "2") (pintype "passive"))
      (node (ref "R40") (pin "2") (pintype "passive"))
      (node (ref "U13") (pin "33") (pinfunction "VDDA_33") (pintype "passive"))
    )
    (net (code "95") (name "GND") (class "Default")
      (node (ref "C12") (pin "1") (pinfunction "1_1") (pintype "passive"))
      (node (ref "C17") (pin "1") (pinfunction "1_1") (pintype "passive"))
      (node (ref "C19") (pin "2") (pinfunction "2_2") (pintype "passive"))
      (node (ref "C23") (pin "1") (pinfunction "1_1") (pintype "passive"))
      (node (ref "C24") (pin "1") (pinfunction "1_1") (pintype "passive"))
      (node (ref "C44") (pin "2") (pinfunction "2_2") (pintype "passive"))
      (node (ref "C45") (pin "1") (pinfunction "1_1") (pintype "passive"))
      (node (ref "C46") (pin "1") (pinfunction "1_1") (pintype "passive"))
      (node (ref "C47") (pin "1") (pinfunction "1_1") (pintype "passive"))
      (node (ref "C48") (pin "1") (pinfunction "1_1") (pintype "passive"))
      (node (ref "C49") (pin "1") (pinfunction "1_1") (pintype "passive"))
      (node (ref "C50") (pin "2") (pinfunction "2_2") (pintype "passive"))
      (node (ref "C51") (pin "1") (pinfunction "1_1") (pintype "passive"))
      (node (ref "C52") (pin "1") (pinfunction "1_1") (pintype "passive"))
      (node (ref "C54") (pin "1") (pinfunction "1_1") (pintype "passive"))
      (node (ref "C55") (pin "1") (pinfunction "1_1") (pintype "passive"))
      (node (ref "C56") (pin "1") (pinfunction "1_1") (pintype "passive"))
      (node (ref "C57") (pin "1") (pinfunction "1_1") (pintype "passive"))
      (node (ref "C58") (pin "1") (pinfunction "1_1") (pintype "passive"))
      (node (ref "C59") (pin "2") (pinfunction "2_2") (pintype "passive"))
      (node (ref "C60") (pin "2") (pinfunction "2_2") (pintype "passive"))
      (node (ref "C70") (pin "1") (pinfunction "1_1") (pintype "passive"))
      (node (ref "C71") (pin "1") (pinfunction "1_1") (pintype "passive"))
      (node (ref "C91") (pin "1") (pinfunction "1_1") (pintype "passive"))
      (node (ref "D1") (pin "1") (pinfunction "1_1") (pintype "passive"))
      (node (ref "D4") (pin "2") (pinfunction "2_2") (pintype "passive"))
      (node (ref "P1") (pin "3") (pinfunction "3_3") (pintype "passive"))
      (node (ref "P12") (pin "1") (pinfunction "BN_1") (pintype "passive"))
      (node (ref "P6") (pin "3") (pinfunction "MOSI/CMD_3") (pintype "passive"))
      (node (ref "P7") (pin "3") (pinfunction "3_3") (pintype "passive"))
      (node (ref "P7") (pin "5") (pinfunction "5_5") (pintype "passive"))
      (node (ref "P7") (pin "9") (pinfunction "9_9") (pintype "passive"))
      (node (ref "Q32") (pin "2") (pinfunction "2_2") (pintype "passive"))
      (node (ref "Q33") (pin "2") (pinfunction "2_2") (pintype "passive"))
      (node (ref "Q34") (pin "2") (pinfunction "2_2") (pintype "passive"))
      (node (ref "Q35") (pin "2") (pinfunction "2_2") (pintype "passive"))
      (node (ref "Q36") (pin "2") (pinfunction "2_2") (pintype "passive"))
      (node (ref "Q37") (pin "2") (pinfunction "2_2") (pintype "passive"))
      (node (ref "R153") (pin "1") (pintype "passive"))
      (node (ref "R64") (pin "1") (pintype "passive"))
      (node (ref "U13") (pin "107") (pinfunction "VSS_107") (pintype "passive"))
      (node (ref "U13") (pin "120") (pinfunction "VSS_120") (pintype "passive"))
      (node (ref "U13") (pin "130") (pinfunction "VSS_130") (pintype "passive"))
      (node (ref "U13") (pin "16") (pinfunction "VSS_16") (pintype "passive"))
      (node (ref "U13") (pin "31") (pinfunction "VSSA_31") (pintype "passive"))
      (node (ref "U13") (pin "38") (pinfunction "VSS_38") (pintype "passive"))
      (node (ref "U13") (pin "51") (pinfunction "VSS_51") (pintype "passive"))
      (node (ref "U13") (pin "61") (pinfunction "VSS_61") (pintype "passive"))
      (node (ref "U13") (pin "83") (pinfunction "VSS_83") (pintype "passive"))
      (node (ref "U13") (pin "94") (pinfunction "VSS_94") (pintype "passive"))
      (node (ref "U18") (pin "1") (pinfunction "E0_1") (pintype "passive"))
      (node (ref "U18") (pin "2") (pinfunction "E1_2") (pintype "passive"))
      (node (ref "U18") (pin "3") (pinfunction "E2_3") (pintype "passive"))
      (node (ref "U18") (pin "4") (pinfunction "VSS_4") (pintype "passive"))
      (node (ref "U46") (pin "7") (pinfunction "GND_7") (pintype "power_in"))
    )
    (net (code "96") (name "Net-(C24-Pad2)") (class "Default")
      (node (ref "C24") (pin "2") (pinfunction "2_2") (pintype "passive"))
      (node (ref "R45") (pin "2") (pintype "passive"))
      (node (ref "X1") (pin "1") (pinfunction "1_1") (pintype "passive"))
    )
    (net (code "97") (name "Net-(LED1-Pad1)") (class "Default")
      (node (ref "LED1") (pin "1") (pinfunction "1_1") (pintype "passive"))
      (node (ref "Q32") (pin "3") (pinfunction "3_3") (pintype "passive"))
    )
    (net (code "98") (name "Net-(LED2-Pad1)") (class "Default")
      (node (ref "LED2") (pin "1") (pinfunction "1_1") (pintype "passive"))
      (node (ref "Q33") (pin "3") (pinfunction "3_3") (pintype "passive"))
    )
    (net (code "99") (name "Net-(LED11-Pad1)") (class "Default")
      (node (ref "LED11") (pin "1") (pinfunction "1_1") (pintype "passive"))
      (node (ref "Q34") (pin "3") (pinfunction "3_3") (pintype "passive"))
    )
    (net (code "100") (name "Net-(LED12-Pad1)") (class "Default")
      (node (ref "LED12") (pin "1") (pinfunction "1_1") (pintype "passive"))
      (node (ref "Q35") (pin "3") (pinfunction "3_3") (pintype "passive"))
    )
    (net (code "101") (name "Net-(LED13-Pad1)") (class "Default")
      (node (ref "LED13") (pin "1") (pinfunction "1_1") (pintype "passive"))
      (node (ref "Q36") (pin "3") (pinfunction "3_3") (pintype "passive"))
    )
    (net (code "102") (name "Net-(LED14-Pad1)") (class "Default")
      (node (ref "LED14") (pin "1") (pinfunction "1_1") (pintype "passive"))
      (node (ref "Q37") (pin "3") (pinfunction "3_3") (pintype "passive"))
    )
    (net (code "103") (name "Net-(Q32-Pad1)") (class "Default")
      (node (ref "Q32") (pin "1") (pinfunction "1_1") (pintype "passive"))
      (node (ref "R79") (pin "2") (pintype "passive"))
    )
    (net (code "104") (name "Net-(Q33-Pad1)") (class "Default")
      (node (ref "Q33") (pin "1") (pinfunction "1_1") (pintype "passive"))
      (node (ref "R80") (pin "2") (pintype "passive"))
    )
    (net (code "105") (name "Net-(Q34-Pad1)") (class "Default")
      (node (ref "Q34") (pin "1") (pinfunction "1_1") (pintype "passive"))
      (node (ref "R95") (pin "2") (pintype "passive"))
    )
    (net (code "106") (name "Net-(Q35-Pad1)") (class "Default")
      (node (ref "Q35") (pin "1") (pinfunction "1_1") (pintype "passive"))
      (node (ref "R96") (pin "2") (pintype "passive"))
    )
    (net (code "107") (name "Net-(Q36-Pad1)") (class "Default")
      (node (ref "Q36") (pin "1") (pinfunction "1_1") (pintype "passive"))
      (node (ref "R114") (pin "2") (pintype "passive"))
    )
    (net (code "108") (name "Net-(Q37-Pad1)") (class "Default")
      (node (ref "Q37") (pin "1") (pinfunction "1_1") (pintype "passive"))
      (node (ref "R115") (pin "2") (pintype "passive"))
    )
    (net (code "109") (name "Net-(U13A-BOOT0)") (class "Default")
      (node (ref "R153") (pin "2") (pintype "passive"))
      (node (ref "U13") (pin "138") (pinfunction "BOOT0_138") (pintype "passive"))
    )
    (net (code "110") (name "Net-(U13A-PC14)") (class "Default")
      (node (ref "C70") (pin "2") (pinfunction "2_2") (pintype "passive"))
      (node (ref "U13") (pin "8") (pinfunction "PC14_8") (pintype "passive"))
      (node (ref "X2") (pin "1") (pinfunction "1_1") (pintype "passive"))
    )
    (net (code "111") (name "Net-(U13A-PC15)") (class "Default")
      (node (ref "C71") (pin "2") (pinfunction "2_2") (pintype "passive"))
      (node (ref "U13") (pin "9") (pinfunction "PC15_9") (pintype "passive"))
      (node (ref "X2") (pin "2") (pinfunction "2_2") (pintype "passive"))
    )
    (net (code "112") (name "Net-(U13A-PDR_ON)") (class "Default")
      (node (ref "R152") (pin "2") (pintype "passive"))
      (node (ref "U13") (pin "143") (pinfunction "PDR_ON_143") (pintype "passive"))
    )
    (net (code "113") (name "Net-(U13A-PH0)") (class "Default")
      (node (ref "R45") (pin "1") (pintype "passive"))
      (node (ref "U13") (pin "23") (pinfunction "PH0_23") (pintype "passive"))
    )
    (net (code "114") (name "Net-(U13A-PH1)") (class "Default")
      (node (ref "C23") (pin "2") (pinfunction "2_2") (pintype "passive"))
      (node (ref "U13") (pin "24") (pinfunction "PH1_24") (pintype "passive"))
      (node (ref "X1") (pin "2") (pinfunction "2_2") (pintype "passive"))
    )
    (net (code "115") (name "Net-(U13B-VCAP_1)") (class "Default")
      (node (ref "C44") (pin "1") (pinfunction "1_1") (pintype "passive"))
      (node (ref "U13") (pin "71") (pinfunction "VCAP_1_71") (pintype "passive"))
    )
    (net (code "116") (name "Net-(U13B-VCAP_2)") (class "Default")
      (node (ref "C59") (pin "1") (pinfunction "1_1") (pintype "passive"))
      (node (ref "U13") (pin "106") (pinfunction "VCAP_2_106") (pintype "passive"))
    )
    (net (code "117") (name "Net-(U13B-VREF+)") (class "Default")
      (node (ref "R40") (pin "1") (pintype "passive"))
      (node (ref "U13") (pin "32") (pinfunction "VREF+_32") (pintype "passive"))
    )
    (net (code "118") (name "VBAT") (class "Default")
      (node (ref "C91") (pin "2") (pinfunction "2_2") (pintype "passive"))
      (node (ref "P12") (pin "2") (pinfunction "BP_2") (pintype "passive"))
      (node (ref "TP20") (pin "4") (pinfunction "4_4") (pintype "passive"))
      (node (ref "U13") (pin "6") (pinfunction "VBAS_6") (pintype "passive"))
    )
    (net (code "119") (name "VCC") (class "Default")
      (node (ref "C12") (pin "2") (pinfunction "2_2") (pintype "passive"))
      (node (ref "C17") (pin "2") (pinfunction "2_2") (pintype "passive"))
      (node (ref "C19") (pin "1") (pinfunction "1_1") (pintype "passive"))
      (node (ref "C45") (pin "2") (pinfunction "2_2") (pintype "passive"))
      (node (ref "C46") (pin "2") (pinfunction "2_2") (pintype "passive"))
      (node (ref "C47") (pin "2") (pinfunction "2_2") (pintype "passive"))
      (node (ref "C48") (pin "2") (pinfunction "2_2") (pintype "passive"))
      (node (ref "C49") (pin "2") (pinfunction "2_2") (pintype "passive"))
      (node (ref "C51") (pin "2") (pinfunction "2_2") (pintype "passive"))
      (node (ref "C52") (pin "2") (pinfunction "2_2") (pintype "passive"))
      (node (ref "C54") (pin "2") (pinfunction "2_2") (pintype "passive"))
      (node (ref "C55") (pin "2") (pinfunction "2_2") (pintype "passive"))
      (node (ref "C56") (pin "2") (pinfunction "2_2") (pintype "passive"))
      (node (ref "C57") (pin "2") (pinfunction "2_2") (pintype "passive"))
      (node (ref "C58") (pin "2") (pinfunction "2_2") (pintype "passive"))
      (node (ref "C60") (pin "1") (pinfunction "1_1") (pintype "passive"))
      (node (ref "D1") (pin "2") (pinfunction "2_2") (pintype "passive"))
      (node (ref "L4") (pin "1") (pintype "passive"))
      (node (ref "LED1") (pin "2") (pinfunction "2_2") (pintype "passive"))
      (node (ref "LED11") (pin "2") (pinfunction "2_2") (pintype "passive"))
      (node (ref "LED12") (pin "2") (pinfunction "2_2") (pintype "passive"))
      (node (ref "LED13") (pin "2") (pinfunction "2_2") (pintype "passive"))
      (node (ref "LED14") (pin "2") (pinfunction "2_2") (pintype "passive"))
      (node (ref "LED2") (pin "2") (pinfunction "2_2") (pintype "passive"))
      (node (ref "P1") (pin "1") (pinfunction "1_1") (pintype "passive"))
      (node (ref "P6") (pin "5") (pinfunction "SCLK/CLK_5") (pintype "passive"))
      (node (ref "P7") (pin "1") (pinfunction "1_1") (pintype "passive"))
      (node (ref "R11") (pin "2") (pintype "passive"))
      (node (ref "R139") (pin "1") (pintype "passive"))
      (node (ref "R140") (pin "1") (pintype "passive"))
      (node (ref "R151") (pin "1") (pintype "passive"))
      (node (ref "R152") (pin "1") (pintype "passive"))
      (node (ref "R57") (pin "2") (pintype "passive"))
      (node (ref "R60") (pin "2") (pintype "passive"))
      (node (ref "R63") (pin "1") (pintype "passive"))
      (node (ref "R65") (pin "1") (pintype "passive"))
      (node (ref "R66") (pin "1") (pintype "passive"))
      (node (ref "R67") (pin "2") (pintype "passive"))
      (node (ref "R68") (pin "2") (pintype "passive"))
      (node (ref "R74") (pin "2") (pintype "passive"))
      (node (ref "R78") (pin "2") (pintype "passive"))
      (node (ref "U13") (pin "108") (pinfunction "VDD_108") (pintype "passive"))
      (node (ref "U13") (pin "121") (pinfunction "VDD_121") (pintype "passive"))
      (node (ref "U13") (pin "131") (pinfunction "VDD_131") (pintype "passive"))
      (node (ref "U13") (pin "144") (pinfunction "VDD_144") (pintype "passive"))
      (node (ref "U13") (pin "17") (pinfunction "VDD_17") (pintype "passive"))
      (node (ref "U13") (pin "30") (pinfunction "VDD_30") (pintype "passive"))
      (node (ref "U13") (pin "39") (pinfunction "VDD_39") (pintype "passive"))
      (node (ref "U13") (pin "52") (pinfunction "VDD_52") (pintype "passive"))
      (node (ref "U13") (pin "62") (pinfunction "VDD_62") (pintype "passive"))
      (node (ref "U13") (pin "72") (pinfunction "VDD_72") (pintype "passive"))
      (node (ref "U13") (pin "84") (pinfunction "VDD_84") (pintype "passive"))
      (node (ref "U13") (pin "95") (pinfunction "VDD_95") (pintype "passive"))
      (node (ref "U18") (pin "8") (pinfunction "VCC_8") (pintype "passive"))
      (node (ref "U46") (pin "14") (pinfunction "VCC_14") (pintype "power_in"))
    )
    (net (code "120") (name "unconnected-(P7-Pad7)") (class "Default")
      (node (ref "P7") (pin "7") (pinfunction "7_7") (pintype "passive+no_connect"))
    )
    (net (code "121") (name "unconnected-(U13A-PA1-Pad35)") (class "Default")
      (node (ref "U13") (pin "35") (pinfunction "PA1_35") (pintype "passive"))
    )
    (net (code "122") (name "unconnected-(U13A-PA2-Pad36)") (class "Default")
      (node (ref "U13") (pin "36") (pinfunction "PA2_36") (pintype "passive"))
    )
    (net (code "123") (name "unconnected-(U13A-PA7-Pad43)") (class "Default")
      (node (ref "U13") (pin "43") (pinfunction "PA7_43") (pintype "passive"))
    )
    (net (code "124") (name "unconnected-(U13A-PA8-Pad100)") (class "Default")
      (node (ref "U13") (pin "100") (pinfunction "PA8_100") (pintype "passive"))
    )
    (net (code "125") (name "unconnected-(U13A-PB2-Pad48)") (class "Default")
      (node (ref "U13") (pin "48") (pinfunction "PB2_48") (pintype "passive"))
    )
    (net (code "126") (name "unconnected-(U13A-PC0-Pad26)") (class "Default")
      (node (ref "U13") (pin "26") (pinfunction "PC0_26") (pintype "passive"))
    )
    (net (code "127") (name "unconnected-(U13A-PC1-Pad27)") (class "Default")
      (node (ref "U13") (pin "27") (pinfunction "PC1_27") (pintype "passive"))
    )
    (net (code "128") (name "unconnected-(U13A-PC4-Pad44)") (class "Default")
      (node (ref "U13") (pin "44") (pinfunction "PC4_44") (pintype "passive"))
    )
    (net (code "129") (name "unconnected-(U13A-PC5-Pad45)") (class "Default")
      (node (ref "U13") (pin "45") (pinfunction "PC5_45") (pintype "passive"))
    )
    (net (code "130") (name "unconnected-(U13A-PD7-Pad123)") (class "Default")
      (node (ref "U13") (pin "123") (pinfunction "PD7_123") (pintype "passive"))
    )
    (net (code "131") (name "unconnected-(U13A-PD10-Pad79)") (class "Default")
      (node (ref "U13") (pin "79") (pinfunction "PD10_79") (pintype "passive"))
    )
    (net (code "132") (name "unconnected-(U13A-PD15-Pad86)") (class "Default")
      (node (ref "U13") (pin "86") (pinfunction "PD15_86") (pintype "passive"))
    )
    (net (code "133") (name "unconnected-(U13A-PE4-Pad3)") (class "Default")
      (node (ref "U13") (pin "3") (pinfunction "PE4_3") (pintype "passive"))
    )
    (net (code "134") (name "unconnected-(U13A-PF11-Pad49)") (class "Default")
      (node (ref "U13") (pin "49") (pinfunction "PF11_49") (pintype "passive"))
    )
    (net (code "135") (name "unconnected-(U13A-PF12-Pad50)") (class "Default")
      (node (ref "U13") (pin "50") (pinfunction "PF12_50") (pintype "passive"))
    )
    (net (code "136") (name "unconnected-(U13A-PG6-Pad91)") (class "Default")
      (node (ref "U13") (pin "91") (pinfunction "PG6_91") (pintype "passive"))
    )
    (net (code "137") (name "unconnected-(U13A-PG7-Pad92)") (class "Default")
      (node (ref "U13") (pin "92") (pinfunction "PG7_92") (pintype "passive"))
    )
    (net (code "138") (name "unconnected-(U13A-PG8-Pad93)") (class "Default")
      (node (ref "U13") (pin "93") (pinfunction "PG8_93") (pintype "passive"))
    )
    (net (code "139") (name "unconnected-(U13A-PG10-Pad125)") (class "Default")
      (node (ref "U13") (pin "125") (pinfunction "PG10_125") (pintype "passive"))
    )
    (net (code "140") (name "unconnected-(U13A-PG11-Pad126)") (class "Default")
      (node (ref "U13") (pin "126") (pinfunction "PG11_126") (pintype "passive"))
    )
    (net (code "141") (name "unconnected-(U13A-PG12-Pad127)") (class "Default")
      (node (ref "U13") (pin "127") (pinfunction "PG12_127") (pintype "passive"))
    )
    (net (code "142") (name "unconnected-(U13A-PG15-Pad132)") (class "Default")
      (node (ref "U13") (pin "132") (pinfunction "PG15_132") (pintype "passive"))
    )
    (net (code "143") (name "unconnected-(U46A-Y-Pad2)") (class "Default")
      (node (ref "U46") (pin "2") (pinfunction "Y_2") (pintype "output"))
    )
    (net (code "144") (name "unconnected-(U46D-Y-Pad8)") (class "Default")
      (node (ref "U46") (pin "8") (pinfunction "Y_8") (pintype "output"))
    )
    (net (code "145") (name "unconnected-(U46E-Y-Pad10)") (class "Default")
      (node (ref "U46") (pin "10") (pinfunction "Y_10") (pintype "output"))
    )
    (net (code "146") (name "unconnected-(U46F-Y-Pad12)") (class "Default")
      (node (ref "U46") (pin "12") (pinfunction "Y_12") (pintype "output"))
    )
  )
)
